# ledBloom.net
KiCad netlist of a schematic drawn in EAGLE
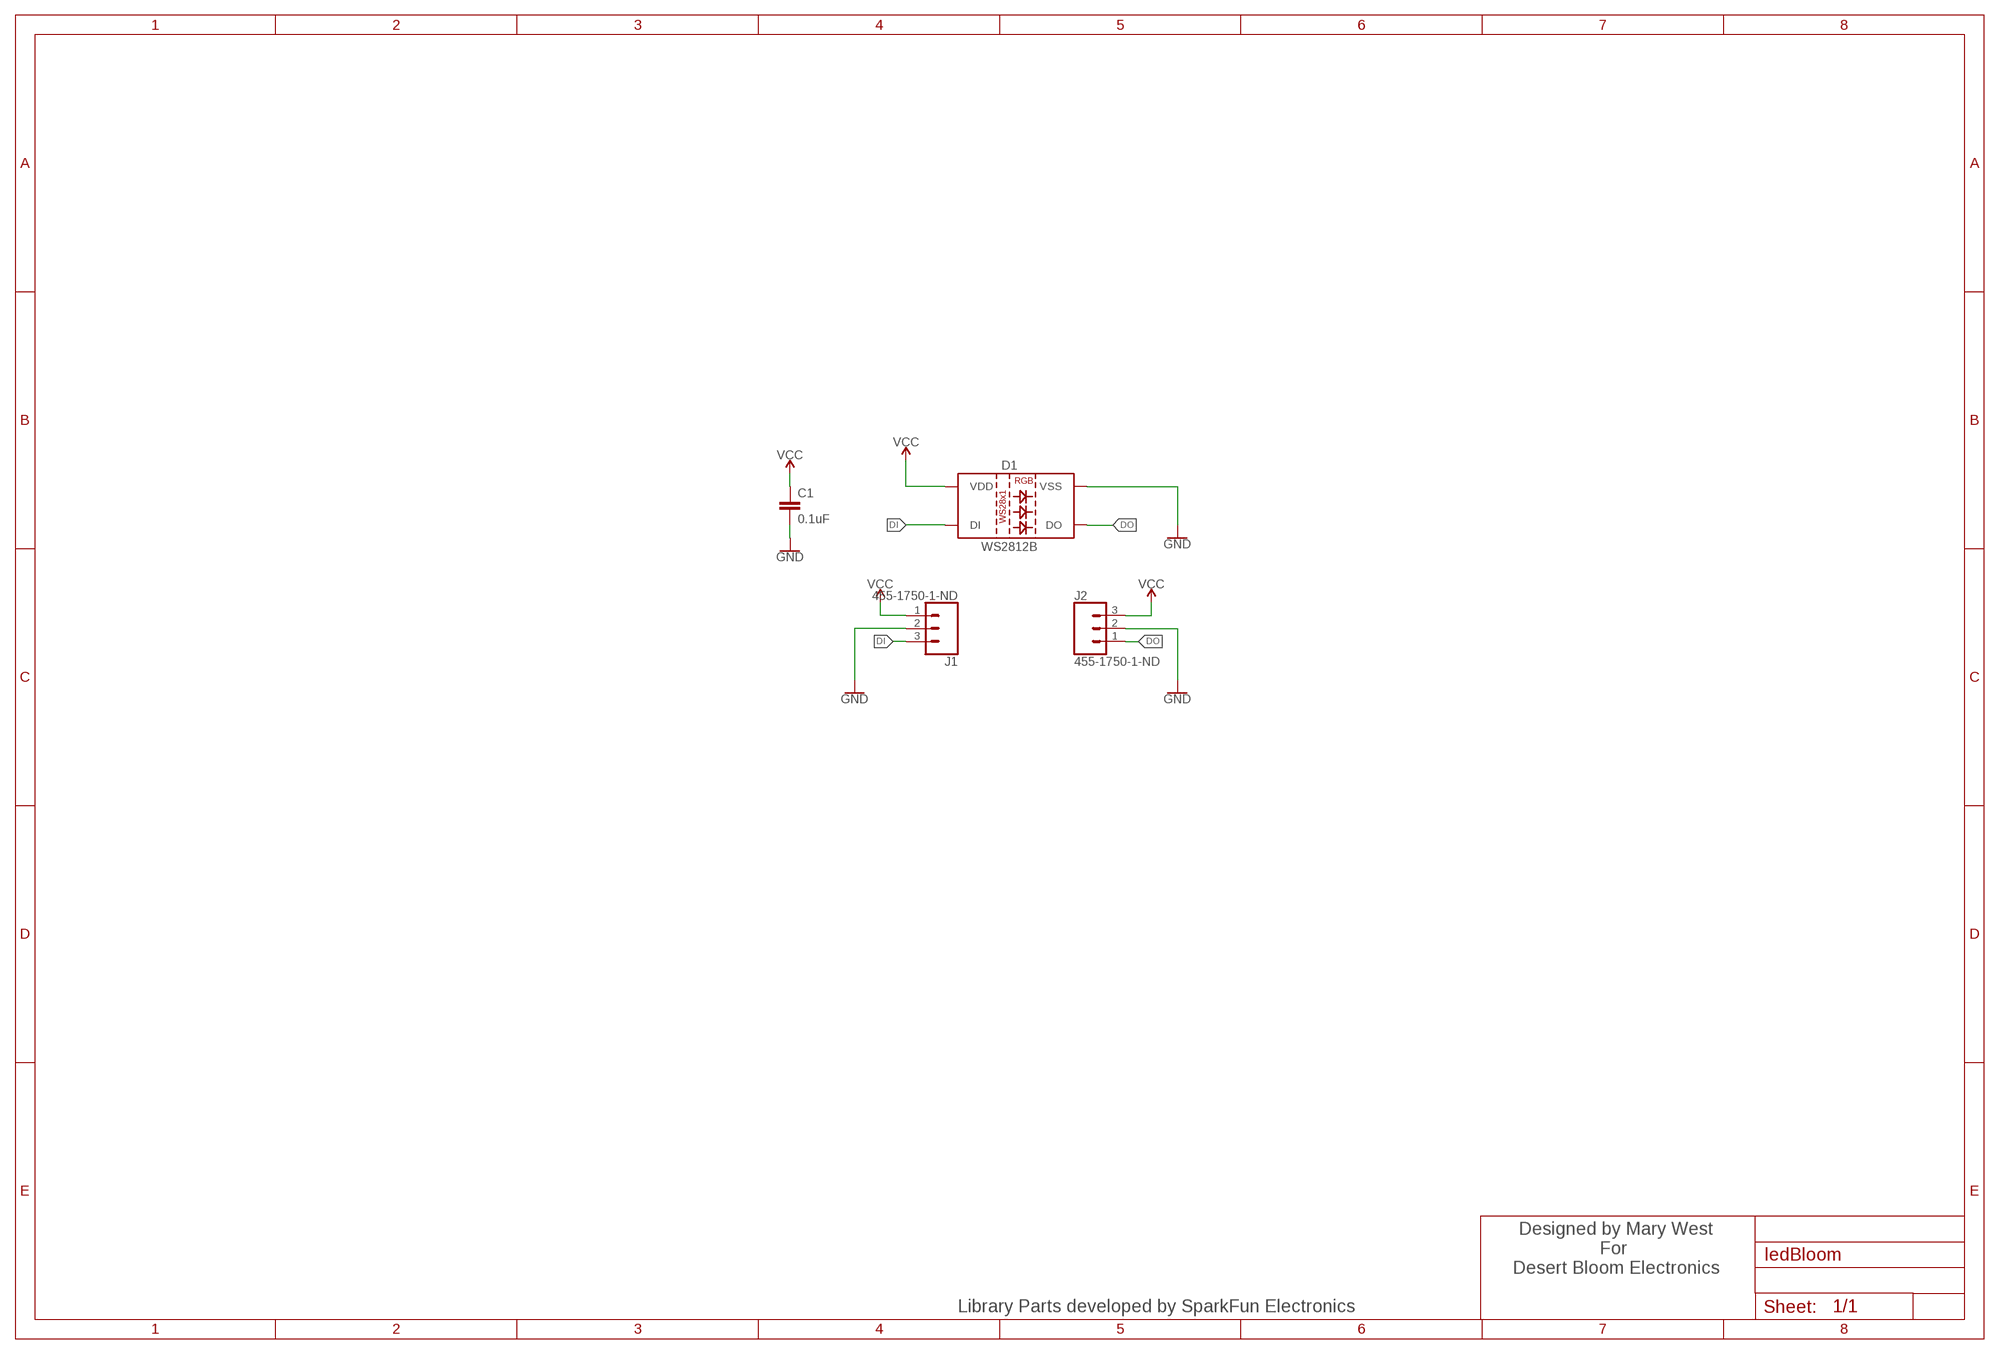
[diagram p0: schematic, sheet 1]

(export (version "E")
  (design (tool "Eeschema 10.0.6"))
  (components
    (comp (ref "C1")
      (value "0.1uF")
      (footprint "eagle-import:0603")
      (libsource (lib "eagle-import") (part "0.1UF-0603-25V-(+80/-20%)"))
    )
    (comp (ref "D1")
      (value "WS2812B")
      (footprint "eagle-import:WS2812B")
      (libsource (lib "eagle-import") (part "WS2812B"))
    )
    (comp (ref "J1")
      (value "455-1750-1-ND")
      (footprint "eagle-import:1X03")
      (libsource (lib "eagle-import") (part "CONN_03"))
    )
    (comp (ref "J2")
      (value "455-1750-1-ND")
      (footprint "eagle-import:1X03")
      (libsource (lib "eagle-import") (part "CONN_03"))
    )
  )
  (nets
    (net (code "1") (name "DI") (class "Default")
      (node (ref "D1") (pin "4") (pinfunction "DI_4") (pintype "bidirectional"))
      (node (ref "J1") (pin "3") (pinfunction "3_3") (pintype "passive"))
    )
    (net (code "2") (name "DO") (class "Default")
      (node (ref "D1") (pin "2") (pinfunction "DO_2") (pintype "bidirectional"))
      (node (ref "J2") (pin "1") (pinfunction "1_1") (pintype "passive"))
    )
    (net (code "3") (name "GND") (class "Default")
      (node (ref "C1") (pin "2") (pinfunction "2_2") (pintype "passive"))
      (node (ref "D1") (pin "3") (pinfunction "VSS_3") (pintype "bidirectional"))
      (node (ref "J1") (pin "2") (pinfunction "2_2") (pintype "passive"))
      (node (ref "J2") (pin "2") (pinfunction "2_2") (pintype "passive"))
    )
    (net (code "4") (name "VCC") (class "Default")
      (node (ref "C1") (pin "1") (pinfunction "1_1") (pintype "passive"))
      (node (ref "D1") (pin "1") (pinfunction "VDD_1") (pintype "bidirectional"))
      (node (ref "J1") (pin "1") (pinfunction "1_1") (pintype "passive"))
      (node (ref "J2") (pin "3") (pinfunction "3_3") (pintype "passive"))
    )
  )
)
